# motordriver-v3_1_IO.net
KiCad netlist of a schematic drawn in Altium Designer
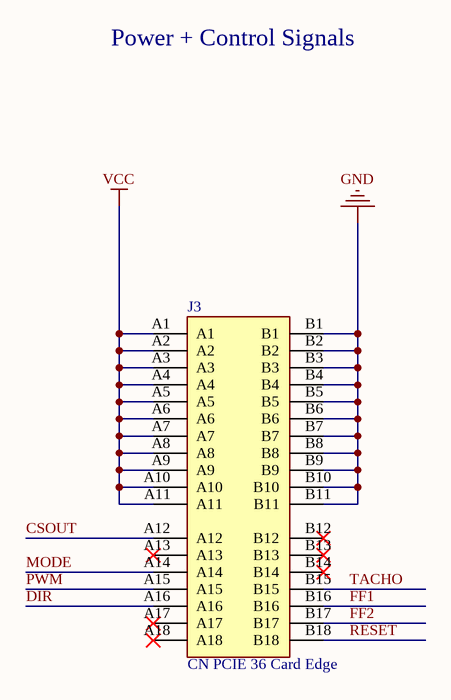
[diagram p0: motordriver-v3.1_IO.SchDoc]

(export (version "E")
  (design (tool "Eeschema 10.0.6"))
  (components
    (comp (ref "J3")
      (value "CN PCIE 36 Card Edge")
      (footprint "CN PCIE EDGE 36CKT")
      (description "36 Position Male PCIE Connector")
      (libsource (lib "AltiumLibraries") (part "CN PCIE 36 Card Edge"))
    )
  )
  (nets
    (net (code "1") (name "/CSOUT") (class "Default")
      (node (ref "J3") (pin "A12") (pinfunction "A12_A12") (pintype "passive"))
    )
    (net (code "2") (name "/DIR") (class "Default")
      (node (ref "J3") (pin "A16") (pinfunction "A16_A16") (pintype "passive"))
    )
    (net (code "3") (name "/FF1") (class "Default")
      (node (ref "J3") (pin "B16") (pinfunction "B16_B16") (pintype "passive"))
    )
    (net (code "4") (name "/FF2") (class "Default")
      (node (ref "J3") (pin "B17") (pinfunction "B17_B17") (pintype "passive"))
    )
    (net (code "5") (name "/MODE") (class "Default")
      (node (ref "J3") (pin "A14") (pinfunction "A14_A14") (pintype "passive"))
    )
    (net (code "6") (name "/PWM") (class "Default")
      (node (ref "J3") (pin "A15") (pinfunction "A15_A15") (pintype "passive"))
    )
    (net (code "7") (name "/RESET") (class "Default")
      (node (ref "J3") (pin "B18") (pinfunction "B18_B18") (pintype "passive"))
    )
    (net (code "8") (name "/TACHO") (class "Default")
      (node (ref "J3") (pin "B15") (pinfunction "B15_B15") (pintype "passive"))
    )
    (net (code "9") (name "GND") (class "Default")
      (node (ref "J3") (pin "B1") (pinfunction "B1_B1") (pintype "passive"))
      (node (ref "J3") (pin "B10") (pinfunction "B10_B10") (pintype "passive"))
      (node (ref "J3") (pin "B11") (pinfunction "B11_B11") (pintype "passive"))
      (node (ref "J3") (pin "B2") (pinfunction "B2_B2") (pintype "passive"))
      (node (ref "J3") (pin "B3") (pinfunction "B3_B3") (pintype "passive"))
      (node (ref "J3") (pin "B4") (pinfunction "B4_B4") (pintype "passive"))
      (node (ref "J3") (pin "B5") (pinfunction "B5_B5") (pintype "passive"))
      (node (ref "J3") (pin "B6") (pinfunction "B6_B6") (pintype "passive"))
      (node (ref "J3") (pin "B7") (pinfunction "B7_B7") (pintype "passive"))
      (node (ref "J3") (pin "B8") (pinfunction "B8_B8") (pintype "passive"))
      (node (ref "J3") (pin "B9") (pinfunction "B9_B9") (pintype "passive"))
    )
    (net (code "10") (name "VCC") (class "Default")
      (node (ref "J3") (pin "A1") (pinfunction "A1_A1") (pintype "passive"))
      (node (ref "J3") (pin "A10") (pinfunction "A10_A10") (pintype "passive"))
      (node (ref "J3") (pin "A11") (pinfunction "A11_A11") (pintype "passive"))
      (node (ref "J3") (pin "A2") (pinfunction "A2_A2") (pintype "passive"))
      (node (ref "J3") (pin "A3") (pinfunction "A3_A3") (pintype "passive"))
      (node (ref "J3") (pin "A4") (pinfunction "A4_A4") (pintype "passive"))
      (node (ref "J3") (pin "A5") (pinfunction "A5_A5") (pintype "passive"))
      (node (ref "J3") (pin "A6") (pinfunction "A6_A6") (pintype "passive"))
      (node (ref "J3") (pin "A7") (pinfunction "A7_A7") (pintype "passive"))
      (node (ref "J3") (pin "A8") (pinfunction "A8_A8") (pintype "passive"))
      (node (ref "J3") (pin "A9") (pinfunction "A9_A9") (pintype "passive"))
    )
    (net (code "11") (name "unconnected-(J3-PadA13)") (class "Default")
      (node (ref "J3") (pin "A13") (pinfunction "A13_A13") (pintype "passive+no_connect"))
    )
    (net (code "12") (name "unconnected-(J3-PadA17)") (class "Default")
      (node (ref "J3") (pin "A17") (pinfunction "A17_A17") (pintype "passive+no_connect"))
    )
    (net (code "13") (name "unconnected-(J3-PadA18)") (class "Default")
      (node (ref "J3") (pin "A18") (pinfunction "A18_A18") (pintype "passive+no_connect"))
    )
    (net (code "14") (name "unconnected-(J3-PadB12)") (class "Default")
      (node (ref "J3") (pin "B12") (pinfunction "B12_B12") (pintype "passive+no_connect"))
    )
    (net (code "15") (name "unconnected-(J3-PadB13)") (class "Default")
      (node (ref "J3") (pin "B13") (pinfunction "B13_B13") (pintype "passive+no_connect"))
    )
    (net (code "16") (name "unconnected-(J3-PadB14)") (class "Default")
      (node (ref "J3") (pin "B14") (pinfunction "B14_B14") (pintype "passive+no_connect"))
    )
  )
)
